# Sheet1.net
KiCad netlist of a schematic drawn in Altium Designer
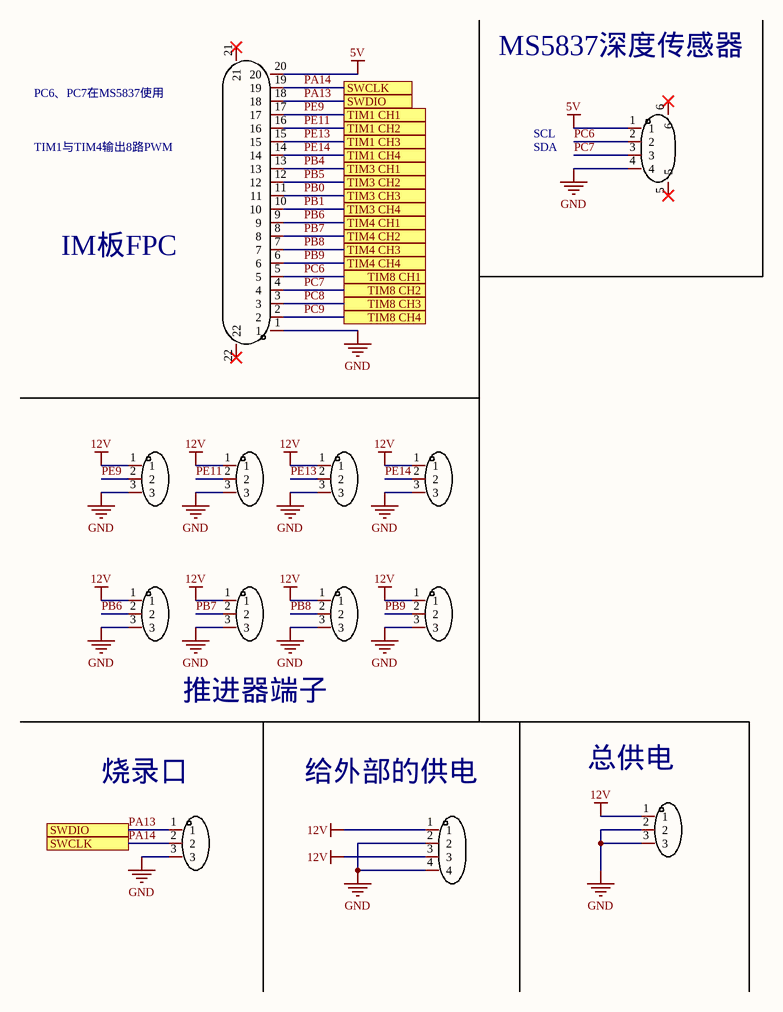
[diagram p0: Sheet1.SchDoc]

(export (version "E")
  (design (tool "Eeschema 10.0.6"))
  (components
    (comp (ref "CN1")
      (value "KF2EDGV-3.81-4P_C441334")
      (footprint "CONN-TH_4P-P3.81_KF2EDGV-3.81-4P")
      (fields (field (name "MANUFACTURER") "KEFA(科发)") (field (name "MANUFACTURER PART") "KF2EDGV-3.81-4P"))
      (libsource (lib "LC_Components") (part "KF2EDGV-3.81-4P_C441334"))
    )
    (comp (ref "FPC")
      (value "FPC-05F-20PH20")
      (footprint "FPC-SMD_20P-P0.50_XUNPU_FPC-05F-20PH20")
      (fields (field (name "MANUFACTURER") "XUNPU(讯普)"))
      (libsource (lib "LC_Components") (part "FPC-05F-20PH20"))
    )
    (comp (ref "MS5837")
      (value "HC-1.25-4PWT")
      (footprint "CONN-SMD_4P-P1.25-HC-1.25-4PWT")
      (fields (field (name "MANUFACTURER") "HCTL(华灿天禄)"))
      (libsource (lib "LC_Components") (part "HC-1.25-4PWT"))
    )
    (comp (ref "PB6")
      (value "MR30-M")
      (footprint "CONN-TH_MR30-M")
      (fields (field (name "MANUFACTURER") "AMASS(艾迈斯)"))
      (libsource (lib "LC_Components") (part "MR30-M"))
    )
    (comp (ref "PB7")
      (value "MR30-M")
      (footprint "CONN-TH_MR30-M")
      (fields (field (name "MANUFACTURER") "AMASS(艾迈斯)"))
      (libsource (lib "LC_Components") (part "MR30-M"))
    )
    (comp (ref "PB8")
      (value "MR30-M")
      (footprint "CONN-TH_MR30-M")
      (fields (field (name "MANUFACTURER") "AMASS(艾迈斯)"))
      (libsource (lib "LC_Components") (part "MR30-M"))
    )
    (comp (ref "PB9")
      (value "MR30-M")
      (footprint "CONN-TH_MR30-M")
      (fields (field (name "MANUFACTURER") "AMASS(艾迈斯)"))
      (libsource (lib "LC_Components") (part "MR30-M"))
    )
    (comp (ref "PE9")
      (value "MR30-M")
      (footprint "CONN-TH_MR30-M")
      (fields (field (name "MANUFACTURER") "AMASS(艾迈斯)"))
      (libsource (lib "LC_Components") (part "MR30-M"))
    )
    (comp (ref "PE11")
      (value "MR30-M")
      (footprint "CONN-TH_MR30-M")
      (fields (field (name "MANUFACTURER") "AMASS(艾迈斯)"))
      (libsource (lib "LC_Components") (part "MR30-M"))
    )
    (comp (ref "PE13")
      (value "MR30-M")
      (footprint "CONN-TH_MR30-M")
      (fields (field (name "MANUFACTURER") "AMASS(艾迈斯)"))
      (libsource (lib "LC_Components") (part "MR30-M"))
    )
    (comp (ref "PE14")
      (value "MR30-M")
      (footprint "CONN-TH_MR30-M")
      (fields (field (name "MANUFACTURER") "AMASS(艾迈斯)"))
      (libsource (lib "LC_Components") (part "MR30-M"))
    )
    (comp (ref "POWER")
      (value "MR30-M")
      (footprint "CONN-TH_MR30-M")
      (fields (field (name "MANUFACTURER") "AMASS(艾迈斯)"))
      (libsource (lib "LC_Components") (part "MR30-M"))
    )
    (comp (ref "SW")
      (value "KF2EDGV-3.81-3P")
      (footprint "CONN-TH_3P-P3.81_KF2EDGV-3.81-3P")
      (fields (field (name "MANUFACTURER") "KEFA(科发)"))
      (libsource (lib "LC_Components") (part "KF2EDGV-3.81-3P"))
    )
  )
  (nets
    (net (code "1") (name "/PA13") (class "Default")
      (node (ref "FPC") (pin "18") (pinfunction "18_18") (pintype "passive"))
      (node (ref "SW") (pin "1") (pinfunction "1_1") (pintype "passive"))
    )
    (net (code "2") (name "/PA14") (class "Default")
      (node (ref "FPC") (pin "19") (pinfunction "19_19") (pintype "passive"))
      (node (ref "SW") (pin "2") (pinfunction "2_2") (pintype "passive"))
    )
    (net (code "3") (name "/PB0") (class "Default")
      (node (ref "FPC") (pin "11") (pinfunction "11_11") (pintype "passive"))
    )
    (net (code "4") (name "/PB1") (class "Default")
      (node (ref "FPC") (pin "10") (pinfunction "10_10") (pintype "passive"))
    )
    (net (code "5") (name "/PB4") (class "Default")
      (node (ref "FPC") (pin "13") (pinfunction "13_13") (pintype "passive"))
    )
    (net (code "6") (name "/PB5") (class "Default")
      (node (ref "FPC") (pin "12") (pinfunction "12_12") (pintype "passive"))
    )
    (net (code "7") (name "/PB6") (class "Default")
      (node (ref "FPC") (pin "9") (pinfunction "9_9") (pintype "passive"))
      (node (ref "PB6") (pin "2") (pinfunction "2_2") (pintype "passive"))
    )
    (net (code "8") (name "/PB7") (class "Default")
      (node (ref "FPC") (pin "8") (pinfunction "8_8") (pintype "passive"))
      (node (ref "PB7") (pin "2") (pinfunction "2_2") (pintype "passive"))
    )
    (net (code "9") (name "/PB8") (class "Default")
      (node (ref "FPC") (pin "7") (pinfunction "7_7") (pintype "passive"))
      (node (ref "PB8") (pin "2") (pinfunction "2_2") (pintype "passive"))
    )
    (net (code "10") (name "/PB9") (class "Default")
      (node (ref "FPC") (pin "6") (pinfunction "6_6") (pintype "passive"))
      (node (ref "PB9") (pin "2") (pinfunction "2_2") (pintype "passive"))
    )
    (net (code "11") (name "/PC6") (class "Default")
      (node (ref "FPC") (pin "5") (pinfunction "5_5") (pintype "passive"))
      (node (ref "MS5837") (pin "2") (pinfunction "2_2") (pintype "passive"))
    )
    (net (code "12") (name "/PC7") (class "Default")
      (node (ref "FPC") (pin "4") (pinfunction "4_4") (pintype "passive"))
      (node (ref "MS5837") (pin "3") (pinfunction "3_3") (pintype "passive"))
    )
    (net (code "13") (name "/PC8") (class "Default")
      (node (ref "FPC") (pin "3") (pinfunction "3_3") (pintype "passive"))
    )
    (net (code "14") (name "/PC9") (class "Default")
      (node (ref "FPC") (pin "2") (pinfunction "2_2") (pintype "passive"))
    )
    (net (code "15") (name "/PE9") (class "Default")
      (node (ref "FPC") (pin "17") (pinfunction "17_17") (pintype "passive"))
      (node (ref "PE9") (pin "2") (pinfunction "2_2") (pintype "passive"))
    )
    (net (code "16") (name "/PE11") (class "Default")
      (node (ref "FPC") (pin "16") (pinfunction "16_16") (pintype "passive"))
      (node (ref "PE11") (pin "2") (pinfunction "2_2") (pintype "passive"))
    )
    (net (code "17") (name "/PE13") (class "Default")
      (node (ref "FPC") (pin "15") (pinfunction "15_15") (pintype "passive"))
      (node (ref "PE13") (pin "2") (pinfunction "2_2") (pintype "passive"))
    )
    (net (code "18") (name "/PE14") (class "Default")
      (node (ref "FPC") (pin "14") (pinfunction "14_14") (pintype "passive"))
      (node (ref "PE14") (pin "2") (pinfunction "2_2") (pintype "passive"))
    )
    (net (code "19") (name "5V") (class "Default")
      (node (ref "FPC") (pin "20") (pinfunction "20_20") (pintype "passive"))
      (node (ref "MS5837") (pin "1") (pinfunction "1_1") (pintype "passive"))
    )
    (net (code "20") (name "12V") (class "Default")
      (node (ref "CN1") (pin "1") (pinfunction "1_1") (pintype "passive"))
      (node (ref "CN1") (pin "3") (pinfunction "3_3") (pintype "passive"))
      (node (ref "PB6") (pin "1") (pinfunction "1_1") (pintype "passive"))
      (node (ref "PB7") (pin "1") (pinfunction "1_1") (pintype "passive"))
      (node (ref "PB8") (pin "1") (pinfunction "1_1") (pintype "passive"))
      (node (ref "PB9") (pin "1") (pinfunction "1_1") (pintype "passive"))
      (node (ref "PE11") (pin "1") (pinfunction "1_1") (pintype "passive"))
      (node (ref "PE13") (pin "1") (pinfunction "1_1") (pintype "passive"))
      (node (ref "PE14") (pin "1") (pinfunction "1_1") (pintype "passive"))
      (node (ref "PE9") (pin "1") (pinfunction "1_1") (pintype "passive"))
      (node (ref "POWER") (pin "1") (pinfunction "1_1") (pintype "passive"))
    )
    (net (code "21") (name "GND") (class "Default")
      (node (ref "CN1") (pin "2") (pinfunction "2_2") (pintype "passive"))
      (node (ref "CN1") (pin "4") (pinfunction "4_4") (pintype "passive"))
      (node (ref "FPC") (pin "1") (pinfunction "1_1") (pintype "passive"))
      (node (ref "MS5837") (pin "4") (pinfunction "4_4") (pintype "passive"))
      (node (ref "PB6") (pin "3") (pinfunction "3_3") (pintype "passive"))
      (node (ref "PB7") (pin "3") (pinfunction "3_3") (pintype "passive"))
      (node (ref "PB8") (pin "3") (pinfunction "3_3") (pintype "passive"))
      (node (ref "PB9") (pin "3") (pinfunction "3_3") (pintype "passive"))
      (node (ref "PE11") (pin "3") (pinfunction "3_3") (pintype "passive"))
      (node (ref "PE13") (pin "3") (pinfunction "3_3") (pintype "passive"))
      (node (ref "PE14") (pin "3") (pinfunction "3_3") (pintype "passive"))
      (node (ref "PE9") (pin "3") (pinfunction "3_3") (pintype "passive"))
      (node (ref "POWER") (pin "2") (pinfunction "2_2") (pintype "passive"))
      (node (ref "POWER") (pin "3") (pinfunction "3_3") (pintype "passive"))
      (node (ref "SW") (pin "3") (pinfunction "3_3") (pintype "passive"))
    )
    (net (code "22") (name "unconnected-(FPC-Pad21)") (class "Default")
      (node (ref "FPC") (pin "21") (pinfunction "21_21") (pintype "passive+no_connect"))
    )
    (net (code "23") (name "unconnected-(FPC-Pad22)") (class "Default")
      (node (ref "FPC") (pin "22") (pinfunction "22_22") (pintype "passive+no_connect"))
    )
    (net (code "24") (name "unconnected-(MS5837-Pad5)") (class "Default")
      (node (ref "MS5837") (pin "5") (pinfunction "5_5") (pintype "passive+no_connect"))
    )
    (net (code "25") (name "unconnected-(MS5837-Pad6)") (class "Default")
      (node (ref "MS5837") (pin "6") (pinfunction "6_6") (pintype "passive+no_connect"))
    )
  )
)
